# power_supply.net
KiCad netlist of a schematic drawn in EAGLE
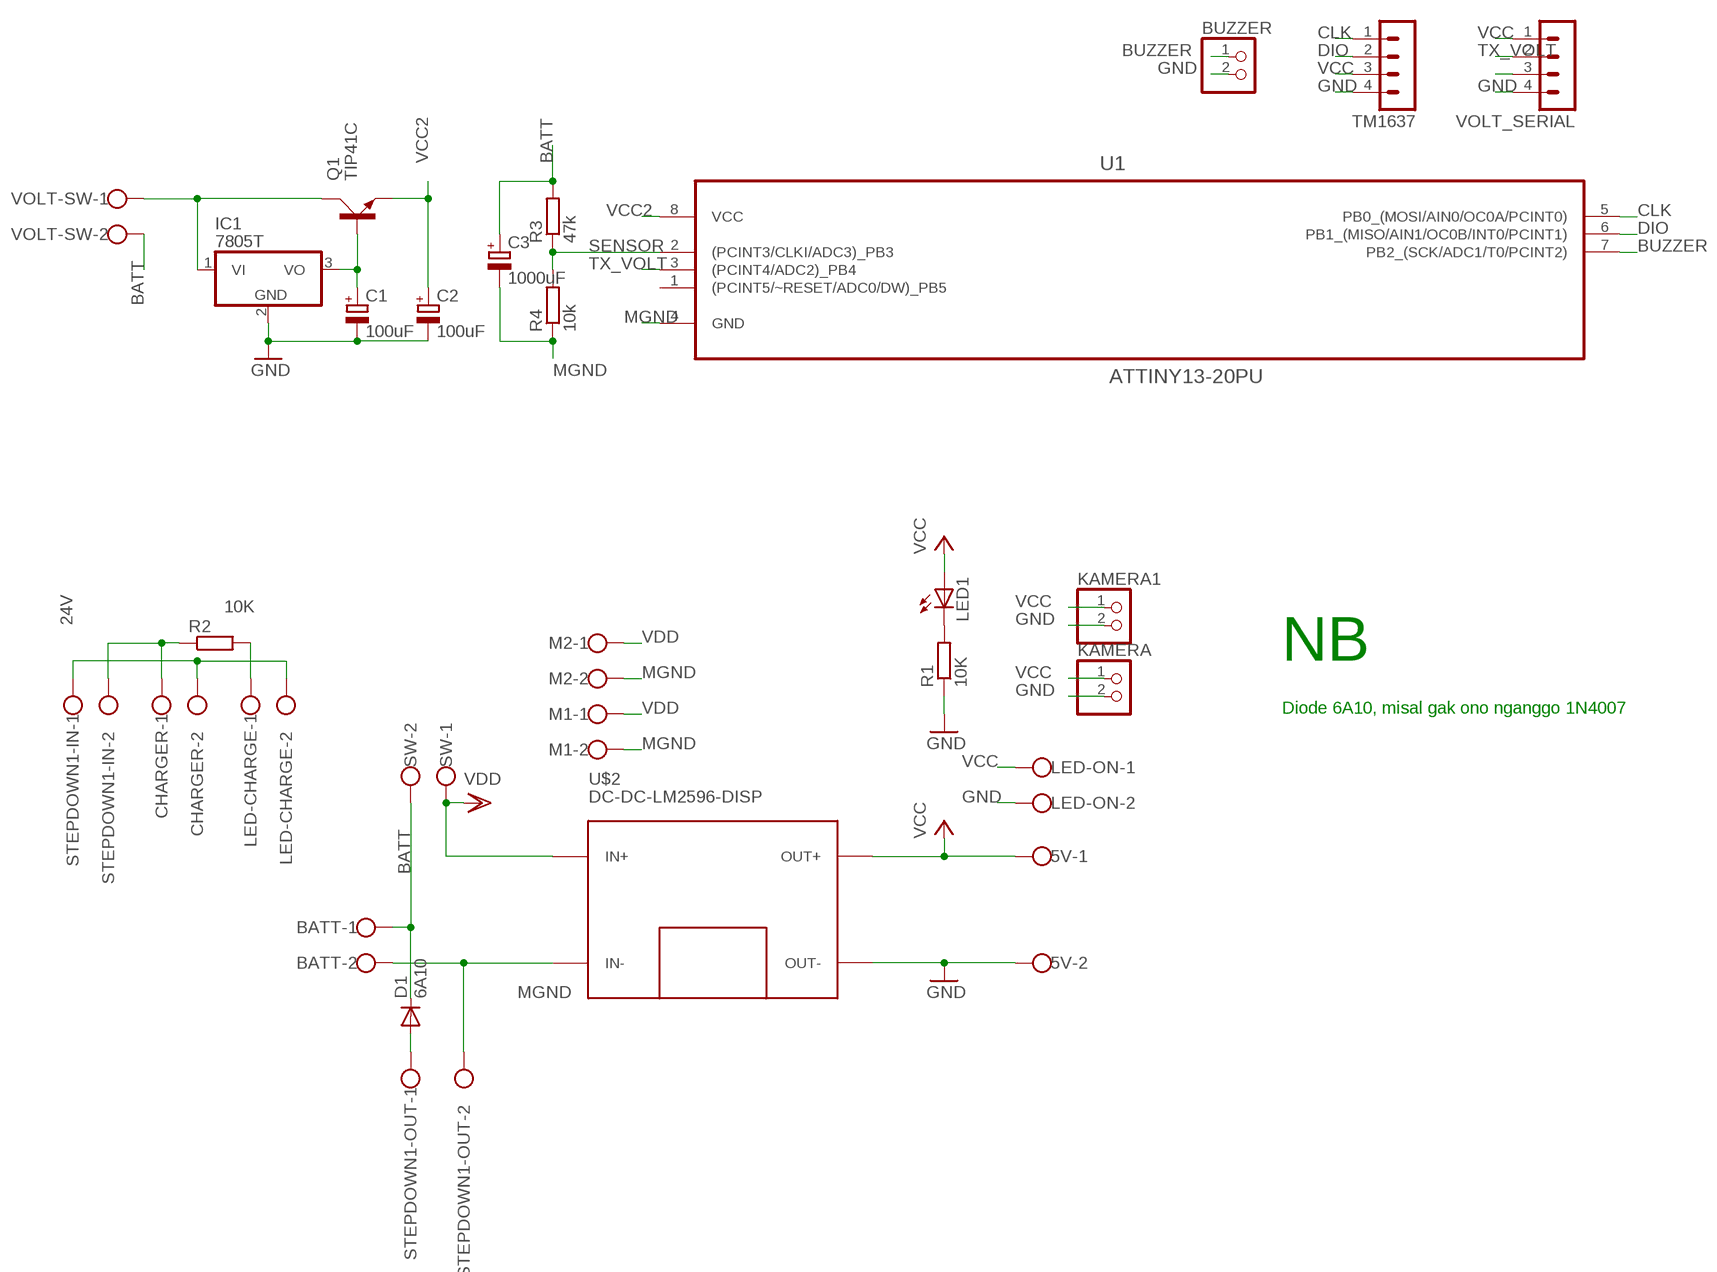
[diagram p0: schematic, sheet 1]

(export (version "E")
  (design (tool "Eeschema 10.0.6"))
  (components
    (comp (ref "5V")
      (value "W237-102")
      (footprint "eagle-import:W237-102")
      (fields (field (name "MPN") "237-102"))
      (libsource (lib "eagle-import") (part "W237-102"))
    )
    (comp (ref "BATT")
      (value "W237-102")
      (footprint "eagle-import:W237-102")
      (fields (field (name "MPN") "237-102"))
      (libsource (lib "eagle-import") (part "W237-102"))
    )
    (comp (ref "BUZZER")
      (value "PINHD-1X2")
      (footprint "eagle-import:1X02")
      (libsource (lib "eagle-import") (part "PINHD-1X2"))
    )
    (comp (ref "C1")
      (value "100uF")
      (footprint "eagle-import:E2-4")
      (libsource (lib "eagle-import") (part "CPOL-EUE2-4"))
    )
    (comp (ref "C2")
      (value "100uF")
      (footprint "eagle-import:E2-4")
      (libsource (lib "eagle-import") (part "CPOL-EUE2-4"))
    )
    (comp (ref "C3")
      (value "1000uF")
      (footprint "eagle-import:ETR4")
      (libsource (lib "eagle-import") (part "resistor_348_CPOL-EUETR4"))
    )
    (comp (ref "CHARGER")
      (value "W237-102")
      (footprint "eagle-import:W237-102")
      (fields (field (name "MPN") "237-102"))
      (libsource (lib "eagle-import") (part "W237-102"))
    )
    (comp (ref "D1")
      (value "6A10")
      (footprint "eagle-import:DO41-10")
      (libsource (lib "eagle-import") (part "1N4004"))
    )
    (comp (ref "IC1")
      (value "7805T")
      (footprint "eagle-import:TO220H")
      (libsource (lib "eagle-import") (part "78T05"))
    )
    (comp (ref "KAMERA")
      (value "PINHD-1X2")
      (footprint "eagle-import:1X02")
      (libsource (lib "eagle-import") (part "PINHD-1X2"))
    )
    (comp (ref "KAMERA1")
      (value "PINHD-1X2")
      (footprint "eagle-import:1X02")
      (libsource (lib "eagle-import") (part "PINHD-1X2"))
    )
    (comp (ref "LED-CHARGE")
      (value "W237-102")
      (footprint "eagle-import:W237-102")
      (fields (field (name "MPN") "237-102"))
      (libsource (lib "eagle-import") (part "W237-102"))
    )
    (comp (ref "LED-ON")
      (value "W237-102")
      (footprint "eagle-import:W237-102")
      (fields (field (name "MPN") "237-102"))
      (libsource (lib "eagle-import") (part "W237-102"))
    )
    (comp (ref "LED1")
      (value "LED5MM")
      (footprint "eagle-import:LED5MM")
      (libsource (lib "eagle-import") (part "LED5MM"))
    )
    (comp (ref "M1")
      (value "W237-102")
      (footprint "eagle-import:W237-102")
      (fields (field (name "MPN") "237-102"))
      (libsource (lib "eagle-import") (part "W237-102"))
    )
    (comp (ref "M2")
      (value "W237-102")
      (footprint "eagle-import:W237-102")
      (fields (field (name "MPN") "237-102"))
      (libsource (lib "eagle-import") (part "W237-102"))
    )
    (comp (ref "Q1")
      (value "TIP41C")
      (footprint "eagle-import:TO220AV")
      (libsource (lib "eagle-import") (part "TIP41C"))
    )
    (comp (ref "R1")
      (value "10K")
      (footprint "eagle-import:0207_10")
      (libsource (lib "eagle-import") (part "R-EU_0207/10"))
    )
    (comp (ref "R2")
      (value "10K")
      (footprint "eagle-import:0617_22")
      (libsource (lib "eagle-import") (part "R-EU_0617/22"))
    )
    (comp (ref "R3")
      (value "47k")
      (footprint "eagle-import:0411_12")
      (libsource (lib "eagle-import") (part "R-EU_0411/12"))
    )
    (comp (ref "R4")
      (value "10k")
      (footprint "eagle-import:0411_12")
      (libsource (lib "eagle-import") (part "R-EU_0411/12"))
    )
    (comp (ref "STEPDOWN1-IN")
      (value "W237-102")
      (footprint "eagle-import:W237-102")
      (fields (field (name "MPN") "237-102"))
      (libsource (lib "eagle-import") (part "W237-102"))
    )
    (comp (ref "STEPDOWN1-OUT")
      (value "W237-102")
      (footprint "eagle-import:W237-102")
      (fields (field (name "MPN") "237-102"))
      (libsource (lib "eagle-import") (part "W237-102"))
    )
    (comp (ref "SW")
      (value "W237-102")
      (footprint "eagle-import:W237-102")
      (fields (field (name "MPN") "237-102"))
      (libsource (lib "eagle-import") (part "W237-102"))
    )
    (comp (ref "TM1637")
      (value "MA04-1")
      (footprint "eagle-import:MA04-1")
      (libsource (lib "eagle-import") (part "MA04-1"))
    )
    (comp (ref "U$2")
      (value "DC-DC-LM2596-DISP")
      (footprint "eagle-import:DC-DC-LM2596-DISP")
      (libsource (lib "eagle-import") (part "DC-DC-LM2596-DISP"))
    )
    (comp (ref "U1")
      (value "ATTINY13-20PU")
      (footprint "eagle-import:DIP254P762X533-8")
      (fields (field (name "MF") "Microchip"))
      (libsource (lib "eagle-import") (part "ATTINY13-20PU"))
    )
    (comp (ref "VOLT-SW")
      (value "W237-102")
      (footprint "eagle-import:W237-102")
      (fields (field (name "MPN") "237-102"))
      (libsource (lib "eagle-import") (part "W237-102"))
    )
    (comp (ref "VOLT_SERIAL")
      (value "MA04-1")
      (footprint "eagle-import:MA04-1")
      (libsource (lib "eagle-import") (part "MA04-1"))
    )
  )
  (nets
    (net (code "1") (name "/24V") (class "Default")
      (node (ref "CHARGER") (pin "1") (pinfunction "KL_1") (pintype "passive"))
      (node (ref "R2") (pin "1") (pinfunction "1_1") (pintype "passive"))
      (node (ref "STEPDOWN1-IN") (pin "2") (pinfunction "KL_2") (pintype "passive"))
    )
    (net (code "2") (name "/BATT") (class "Default")
      (node (ref "BATT") (pin "1") (pinfunction "KL_1") (pintype "passive"))
      (node (ref "C3") (pin "+") (pinfunction "+_+") (pintype "passive"))
      (node (ref "D1") (pin "C") (pinfunction "C_C") (pintype "passive"))
      (node (ref "R3") (pin "2") (pinfunction "2_2") (pintype "passive"))
      (node (ref "SW") (pin "2") (pinfunction "KL_2") (pintype "passive"))
      (node (ref "VOLT-SW") (pin "2") (pinfunction "KL_2") (pintype "passive"))
    )
    (net (code "3") (name "/BUZZER") (class "Default")
      (node (ref "BUZZER") (pin "1") (pinfunction "1_1") (pintype "passive"))
      (node (ref "U1") (pin "7") (pinfunction "PB2_(SCK/ADC1/T0/PCINT2)_7") (pintype "bidirectional"))
    )
    (net (code "4") (name "/CLK") (class "Default")
      (node (ref "TM1637") (pin "1") (pinfunction "1_1") (pintype "passive"))
      (node (ref "U1") (pin "5") (pinfunction "PB0_(MOSI/AIN0/OC0A/PCINT0)_5") (pintype "bidirectional"))
    )
    (net (code "5") (name "/DIO") (class "Default")
      (node (ref "TM1637") (pin "2") (pinfunction "2_2") (pintype "passive"))
      (node (ref "U1") (pin "6") (pinfunction "PB1_(MISO/AIN1/OC0B/INT0/PCINT1)_6") (pintype "bidirectional"))
    )
    (net (code "6") (name "/MGND") (class "Default")
      (node (ref "BATT") (pin "2") (pinfunction "KL_2") (pintype "passive"))
      (node (ref "C3") (pin "-") (pinfunction "-_-") (pintype "passive"))
      (node (ref "M1") (pin "2") (pinfunction "KL_2") (pintype "passive"))
      (node (ref "M2") (pin "2") (pinfunction "KL_2") (pintype "passive"))
      (node (ref "R4") (pin "1") (pinfunction "1_1") (pintype "passive"))
      (node (ref "STEPDOWN1-OUT") (pin "2") (pinfunction "KL_2") (pintype "passive"))
      (node (ref "U$2") (pin "IN-") (pinfunction "IN-_IN-") (pintype "bidirectional"))
      (node (ref "U1") (pin "4") (pinfunction "GND_4") (pintype "passive"))
    )
    (net (code "7") (name "/SENSOR") (class "Default")
      (node (ref "R3") (pin "1") (pinfunction "1_1") (pintype "passive"))
      (node (ref "R4") (pin "2") (pinfunction "2_2") (pintype "passive"))
      (node (ref "U1") (pin "2") (pinfunction "(PCINT3/CLKI/ADC3)_PB3_2") (pintype "bidirectional"))
    )
    (net (code "8") (name "/TX_VOLT") (class "Default")
      (node (ref "U1") (pin "3") (pinfunction "(PCINT4/ADC2)_PB4_3") (pintype "bidirectional"))
      (node (ref "VOLT_SERIAL") (pin "2") (pinfunction "2_2") (pintype "passive"))
    )
    (net (code "9") (name "/VCC2") (class "Default")
      (node (ref "C2") (pin "+") (pinfunction "+_+") (pintype "passive"))
      (node (ref "Q1") (pin "E") (pinfunction "E_E") (pintype "passive"))
      (node (ref "U1") (pin "8") (pinfunction "VCC_8") (pintype "power_in"))
    )
    (net (code "10") (name "GND") (class "Default")
      (node (ref "5V") (pin "2") (pinfunction "KL_2") (pintype "passive"))
      (node (ref "BUZZER") (pin "2") (pinfunction "2_2") (pintype "passive"))
      (node (ref "C1") (pin "-") (pinfunction "-_-") (pintype "passive"))
      (node (ref "C2") (pin "-") (pinfunction "-_-") (pintype "passive"))
      (node (ref "IC1") (pin "2") (pinfunction "GND_2") (pintype "passive"))
      (node (ref "KAMERA") (pin "2") (pinfunction "2_2") (pintype "passive"))
      (node (ref "KAMERA1") (pin "2") (pinfunction "2_2") (pintype "passive"))
      (node (ref "LED-ON") (pin "2") (pinfunction "KL_2") (pintype "passive"))
      (node (ref "R1") (pin "1") (pinfunction "1_1") (pintype "passive"))
      (node (ref "TM1637") (pin "4") (pinfunction "4_4") (pintype "passive"))
      (node (ref "U$2") (pin "OUT-") (pinfunction "OUT-_OUT-") (pintype "bidirectional"))
      (node (ref "VOLT_SERIAL") (pin "4") (pinfunction "4_4") (pintype "passive"))
    )
    (net (code "11") (name "Net-(CHARGERB-KL)") (class "Default")
      (node (ref "CHARGER") (pin "2") (pinfunction "KL_2") (pintype "passive"))
      (node (ref "LED-CHARGE") (pin "2") (pinfunction "KL_2") (pintype "passive"))
      (node (ref "STEPDOWN1-IN") (pin "1") (pinfunction "KL_1") (pintype "passive"))
    )
    (net (code "12") (name "Net-(IC1-VI)") (class "Default")
      (node (ref "IC1") (pin "1") (pinfunction "VI_1") (pintype "input"))
      (node (ref "Q1") (pin "C") (pinfunction "C_C") (pintype "passive"))
      (node (ref "VOLT-SW") (pin "1") (pinfunction "KL_1") (pintype "passive"))
    )
    (net (code "13") (name "Net-(IC1-VO)") (class "Default")
      (node (ref "C1") (pin "+") (pinfunction "+_+") (pintype "passive"))
      (node (ref "IC1") (pin "3") (pinfunction "VO_3") (pintype "passive"))
      (node (ref "Q1") (pin "B") (pinfunction "B_B") (pintype "passive"))
    )
    (net (code "14") (name "Net-(LED-CHARGEA-KL)") (class "Default")
      (node (ref "LED-CHARGE") (pin "1") (pinfunction "KL_1") (pintype "passive"))
      (node (ref "R2") (pin "2") (pinfunction "2_2") (pintype "passive"))
    )
    (net (code "15") (name "Net-(LED1-C)") (class "Default")
      (node (ref "LED1") (pin "K") (pinfunction "C_K") (pintype "passive"))
      (node (ref "R1") (pin "2") (pinfunction "2_2") (pintype "passive"))
    )
    (net (code "16") (name "Net-(STEPDOWN1-OUTA-KL)") (class "Default")
      (node (ref "D1") (pin "A") (pinfunction "A_A") (pintype "passive"))
      (node (ref "STEPDOWN1-OUT") (pin "1") (pinfunction "KL_1") (pintype "passive"))
    )
    (net (code "17") (name "VCC") (class "Default")
      (node (ref "5V") (pin "1") (pinfunction "KL_1") (pintype "passive"))
      (node (ref "KAMERA") (pin "1") (pinfunction "1_1") (pintype "passive"))
      (node (ref "KAMERA1") (pin "1") (pinfunction "1_1") (pintype "passive"))
      (node (ref "LED-ON") (pin "1") (pinfunction "KL_1") (pintype "passive"))
      (node (ref "LED1") (pin "A") (pinfunction "A_A") (pintype "passive"))
      (node (ref "TM1637") (pin "3") (pinfunction "3_3") (pintype "passive"))
      (node (ref "U$2") (pin "OUT+") (pinfunction "OUT+_OUT+") (pintype "bidirectional"))
      (node (ref "VOLT_SERIAL") (pin "1") (pinfunction "1_1") (pintype "passive"))
    )
    (net (code "18") (name "VDD") (class "Default")
      (node (ref "M1") (pin "1") (pinfunction "KL_1") (pintype "passive"))
      (node (ref "M2") (pin "1") (pinfunction "KL_1") (pintype "passive"))
      (node (ref "SW") (pin "1") (pinfunction "KL_1") (pintype "passive"))
      (node (ref "U$2") (pin "IN+") (pinfunction "IN+_IN+") (pintype "bidirectional"))
    )
    (net (code "19") (name "unconnected-(U1-(PCINT5{slash}~{RESET{slash}ADC0{slash}DW})_PB5-Pad1)") (class "Default")
      (node (ref "U1") (pin "1") (pinfunction "(PCINT5/~{RESET/ADC0/DW})_PB5_1") (pintype "bidirectional"))
    )
    (net (code "20") (name "unconnected-(VOLT_SERIAL-Pad3)") (class "Default")
      (node (ref "VOLT_SERIAL") (pin "3") (pinfunction "3_3") (pintype "passive"))
    )
  )
)
